# Sheet3.net
KiCad netlist of a schematic drawn in Altium Designer
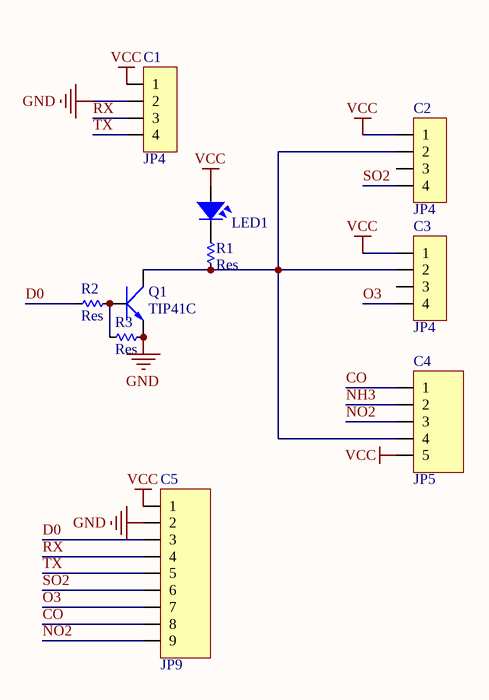
[diagram p0: Sheet3.SchDoc]

(export (version "E")
  (design (tool "Eeschema 10.0.6"))
  (components
    (comp (ref "C1")
      (value "JP4")
      (footprint "JP4-C1T")
      (description "WR-PHD 2.54 mm Angled Socket Header")
      (fields
        (field (name "MANUFACTURER") "Würth Elektronik eiSos GmbH")
        (field (name "PARTNO") "613004143121")
        (field (name "CREATED BY") "Karrer Zheng")
      )
      (libsource (lib "LIBRARY") (part "JP4"))
    )
    (comp (ref "C2")
      (value "JP4")
      (footprint "JP4-C1T")
      (description "WR-PHD 2.54 mm Angled Socket Header")
      (fields
        (field (name "MANUFACTURER") "Würth Elektronik eiSos GmbH")
        (field (name "PARTNO") "613004143121")
        (field (name "CREATED BY") "Karrer Zheng")
      )
      (libsource (lib "LIBRARY") (part "JP4"))
    )
    (comp (ref "C3")
      (value "JP4")
      (footprint "JP4-C1T")
      (description "WR-PHD 2.54 mm Angled Socket Header")
      (fields
        (field (name "MANUFACTURER") "Würth Elektronik eiSos GmbH")
        (field (name "PARTNO") "613004143121")
        (field (name "CREATED BY") "Karrer Zheng")
      )
      (libsource (lib "LIBRARY") (part "JP4"))
    )
    (comp (ref "C4")
      (value "JP5")
      (footprint "JP5-C1T")
      (description "WR-PHD 2.54 mm Angled Socket Header")
      (fields
        (field (name "MANUFACTURER") "Würth Elektronik eiSos GmbH")
        (field (name "PARTNO") "613005143121")
        (field (name "CREATED BY") "Karrer Zheng")
      )
      (libsource (lib "LIBRARY") (part "JP5"))
    )
    (comp (ref "C5")
      (value "JP9")
      (footprint "JP9-D1T")
      (description "WR-PHD 2.54 mm Angled Socket Header")
      (fields
        (field (name "MANUFACTURER") "Würth Elektronik eiSos GmbH")
        (field (name "PARTNO") "613009143121")
        (field (name "CREATED BY") "Karrer Zheng")
      )
      (libsource (lib "LIBRARY") (part "JP9"))
    )
    (comp (ref "LED1")
      (value "LED")
      (footprint "LED-5-BLUE")
      (description "LED Single colour Green and Red")
      (libsource (lib "LIBRARY") (part "LED"))
    )
    (comp (ref "Q1")
      (value "TIP41C")
      (footprint "TO220-123")
      (description "NPN 2W, BCE")
      (libsource (lib "LIBRARY") (part "TIP41C"))
    )
    (comp (ref "R1")
      (value "Res")
      (footprint "RES-1/8WD")
      (fields
        (field (name "MANUFACTURER") "Generic Components")
        (field (name "PUBLISHER") "Altium Hobart Technology Centre")
      )
      (libsource (lib "LIBRARY") (part "Res"))
    )
    (comp (ref "R2")
      (value "Res")
      (footprint "RES-1/8WD")
      (fields
        (field (name "MANUFACTURER") "Generic Components")
        (field (name "PUBLISHER") "Altium Hobart Technology Centre")
      )
      (libsource (lib "LIBRARY") (part "Res"))
    )
    (comp (ref "R3")
      (value "Res")
      (footprint "RES-1/8WD")
      (fields
        (field (name "MANUFACTURER") "Generic Components")
        (field (name "PUBLISHER") "Altium Hobart Technology Centre")
      )
      (libsource (lib "LIBRARY") (part "Res"))
    )
  )
  (nets
    (net (code "1") (name "/CO") (class "Default")
      (node (ref "C4") (pin "1") (pinfunction "1_1") (pintype "passive"))
      (node (ref "C5") (pin "8") (pinfunction "8_8") (pintype "passive"))
    )
    (net (code "2") (name "/D0") (class "Default")
      (node (ref "C5") (pin "3") (pinfunction "3_3") (pintype "passive"))
      (node (ref "R2") (pin "2") (pinfunction "2_2") (pintype "passive"))
    )
    (net (code "3") (name "/NH3") (class "Default")
      (node (ref "C4") (pin "2") (pinfunction "2_2") (pintype "passive"))
    )
    (net (code "4") (name "/NO2") (class "Default")
      (node (ref "C4") (pin "3") (pinfunction "3_3") (pintype "passive"))
      (node (ref "C5") (pin "9") (pinfunction "9_9") (pintype "passive"))
    )
    (net (code "5") (name "/O3") (class "Default")
      (node (ref "C3") (pin "4") (pinfunction "4_4") (pintype "passive"))
      (node (ref "C5") (pin "7") (pinfunction "7_7") (pintype "passive"))
    )
    (net (code "6") (name "/RX") (class "Default")
      (node (ref "C1") (pin "3") (pinfunction "3_3") (pintype "passive"))
      (node (ref "C5") (pin "4") (pinfunction "4_4") (pintype "passive"))
    )
    (net (code "7") (name "/SO2") (class "Default")
      (node (ref "C2") (pin "4") (pinfunction "4_4") (pintype "passive"))
      (node (ref "C5") (pin "6") (pinfunction "6_6") (pintype "passive"))
    )
    (net (code "8") (name "/TX") (class "Default")
      (node (ref "C1") (pin "4") (pinfunction "4_4") (pintype "passive"))
      (node (ref "C5") (pin "5") (pinfunction "5_5") (pintype "passive"))
    )
    (net (code "9") (name "GND") (class "Default")
      (node (ref "C1") (pin "2") (pinfunction "2_2") (pintype "passive"))
      (node (ref "C5") (pin "2") (pinfunction "2_2") (pintype "passive"))
      (node (ref "Q1") (pin "3") (pinfunction "E_3") (pintype "passive"))
      (node (ref "R3") (pin "1") (pinfunction "1_1") (pintype "passive"))
    )
    (net (code "10") (name "Net-(LED1-Pad2)") (class "Default")
      (node (ref "LED1") (pin "2") (pinfunction "2_2") (pintype "passive"))
      (node (ref "R1") (pin "1") (pinfunction "1_1") (pintype "passive"))
    )
    (net (code "11") (name "Net-(Q1-B)") (class "Default")
      (node (ref "Q1") (pin "1") (pinfunction "B_1") (pintype "passive"))
      (node (ref "R2") (pin "1") (pinfunction "1_1") (pintype "passive"))
      (node (ref "R3") (pin "2") (pinfunction "2_2") (pintype "passive"))
    )
    (net (code "12") (name "Net-(Q1-C)") (class "Default")
      (node (ref "C2") (pin "2") (pinfunction "2_2") (pintype "passive"))
      (node (ref "C3") (pin "2") (pinfunction "2_2") (pintype "passive"))
      (node (ref "C4") (pin "4") (pinfunction "4_4") (pintype "passive"))
      (node (ref "Q1") (pin "2") (pinfunction "C_2") (pintype "passive"))
      (node (ref "R1") (pin "2") (pinfunction "2_2") (pintype "passive"))
    )
    (net (code "13") (name "VCC") (class "Default")
      (node (ref "C1") (pin "1") (pinfunction "1_1") (pintype "passive"))
      (node (ref "C2") (pin "1") (pinfunction "1_1") (pintype "passive"))
      (node (ref "C3") (pin "1") (pinfunction "1_1") (pintype "passive"))
      (node (ref "C4") (pin "5") (pinfunction "5_5") (pintype "passive"))
      (node (ref "C5") (pin "1") (pinfunction "1_1") (pintype "passive"))
      (node (ref "LED1") (pin "1") (pinfunction "1_1") (pintype "passive"))
    )
    (net (code "14") (name "unconnected-(C2-Pad3)") (class "Default")
      (node (ref "C2") (pin "3") (pinfunction "3_3") (pintype "passive"))
    )
    (net (code "15") (name "unconnected-(C3-Pad3)") (class "Default")
      (node (ref "C3") (pin "3") (pinfunction "3_3") (pintype "passive"))
    )
  )
)
